# 23_e.net
KiCad netlist of a schematic drawn in EasyEDA Pro
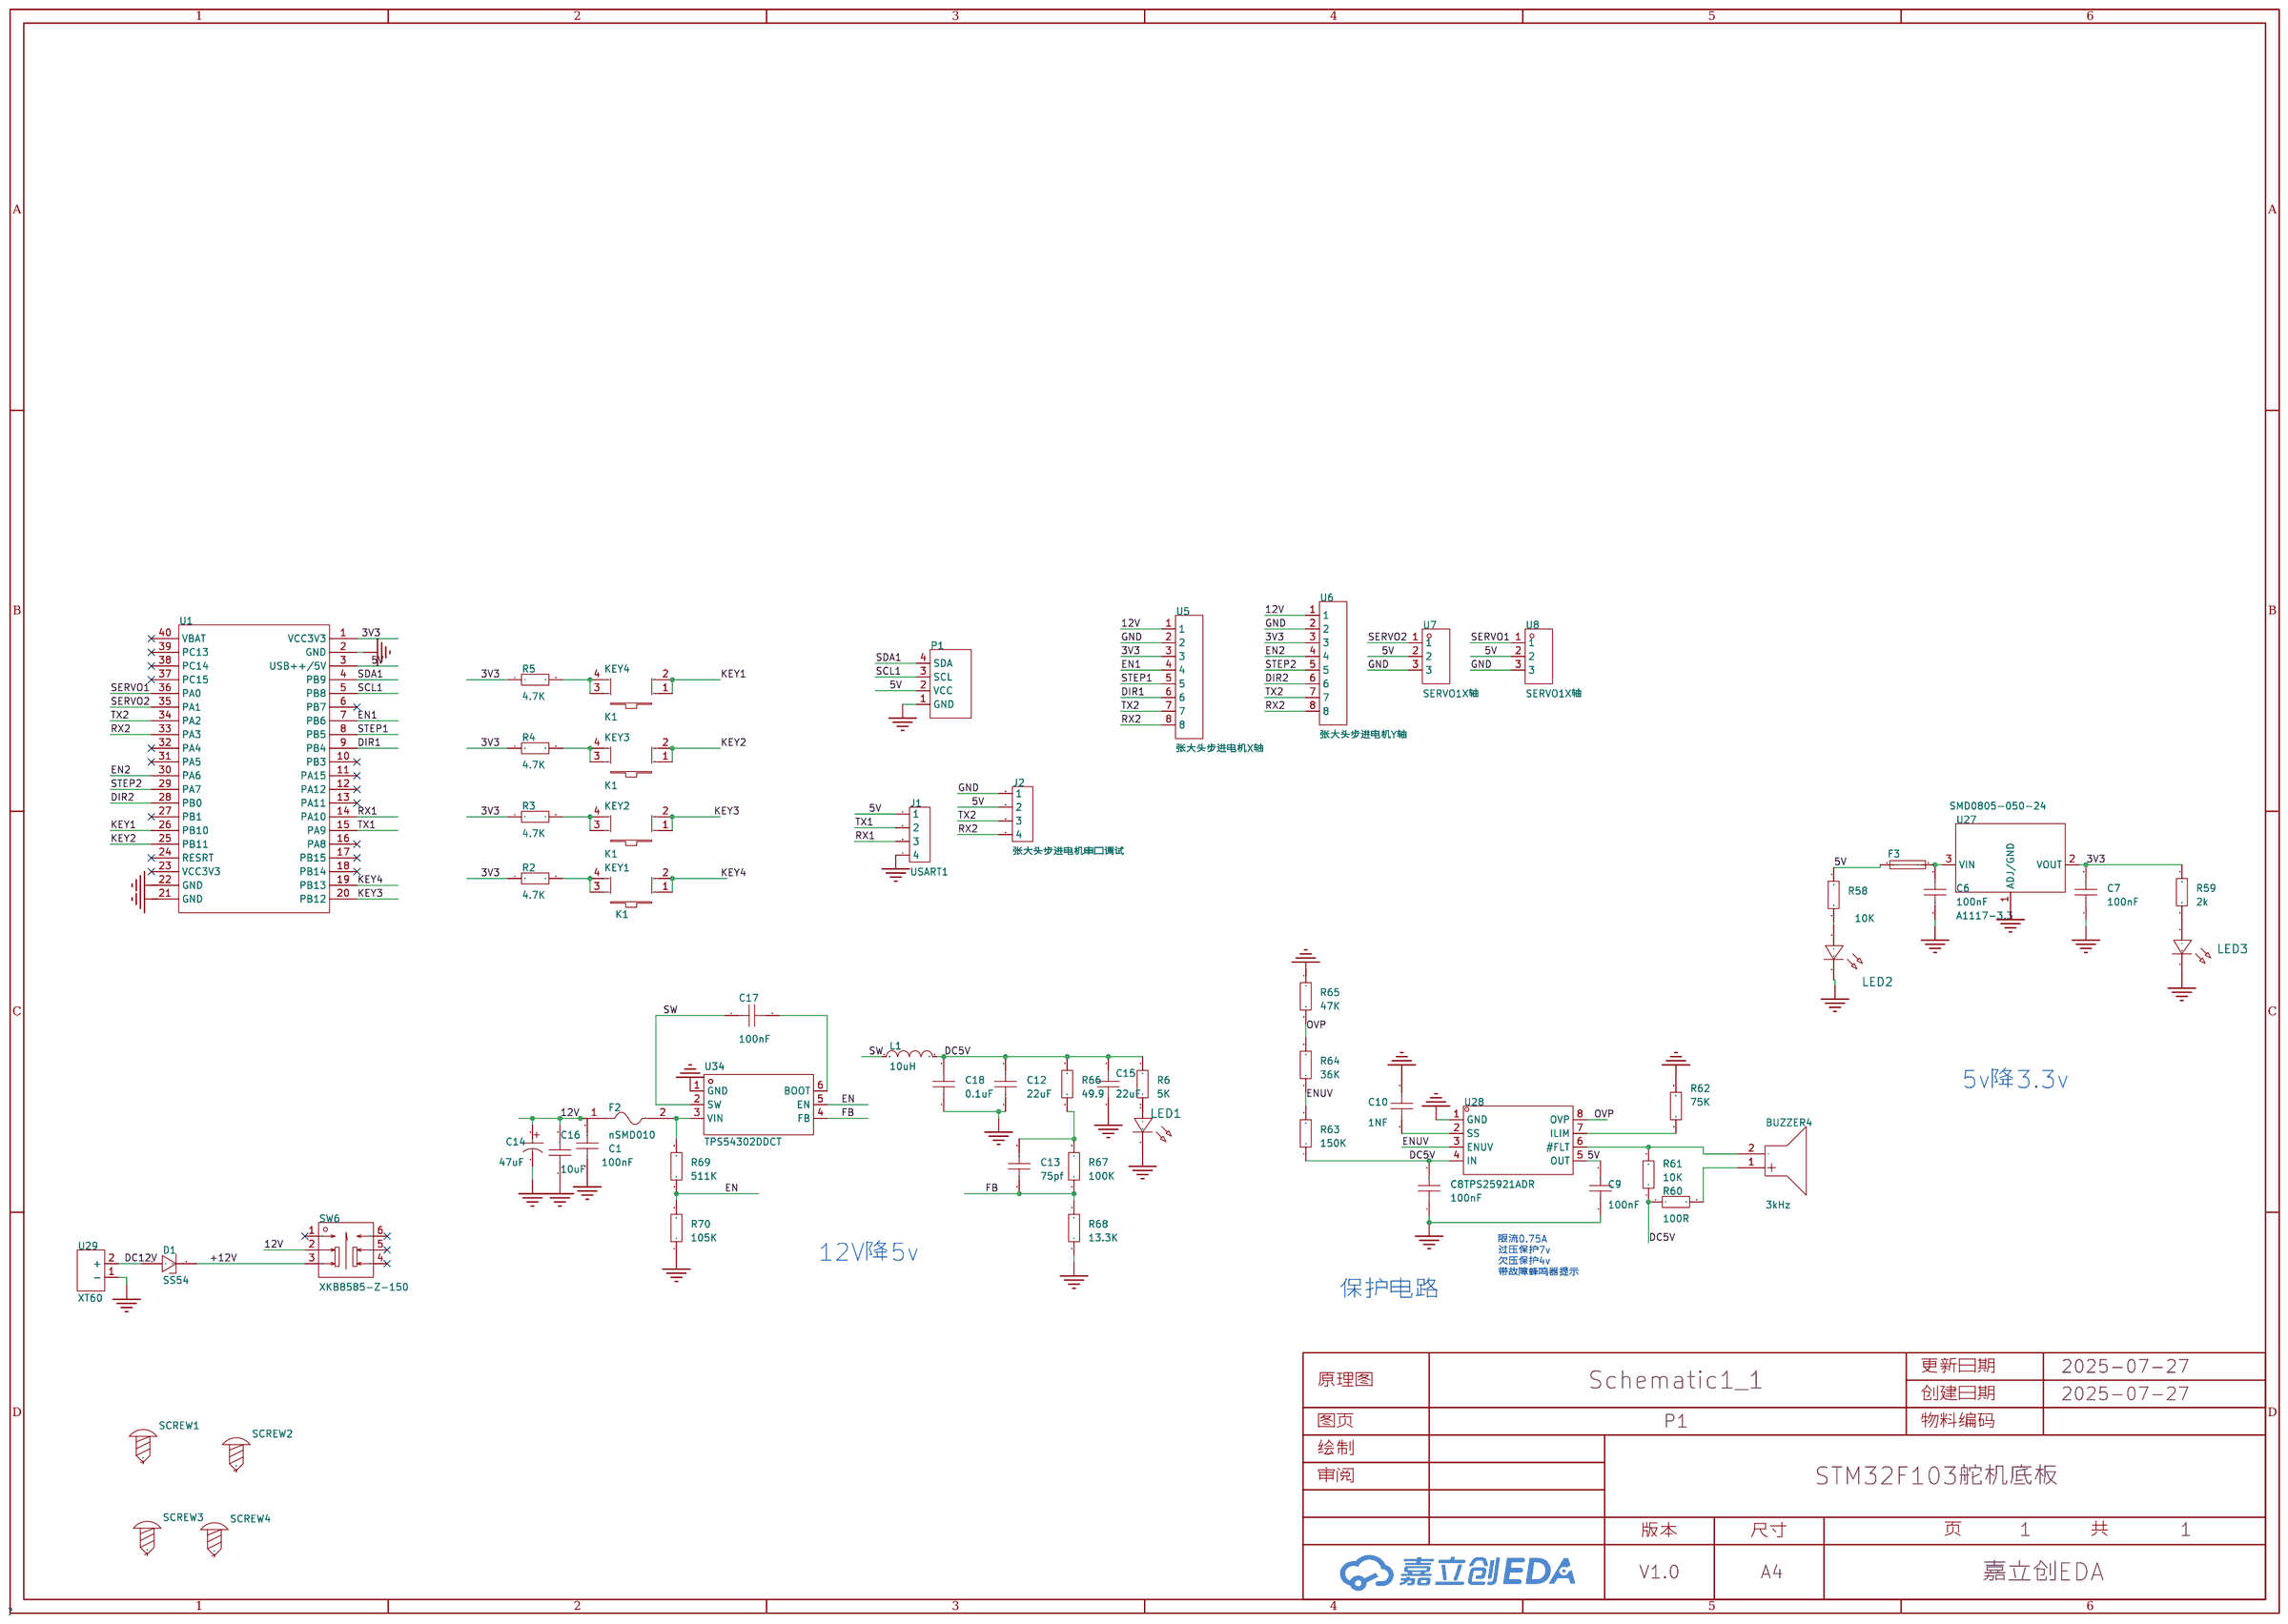
[diagram p0: schematic sheet]

(export (version "E")
  (design (tool "Eeschema 10.0.6"))
  (components
    (comp (ref "BUZZER4")
      (value "3kHz")
      (footprint "easyedapro:BUZ-TH_BD9.0-P5.00-D0.6-FD")
      (description "驱动方式:有源(内含驱动线路);构造类型:电磁式;频率:3kHz;声压(SPL):85dB;")
      (fields (field (name "Manufacturer Part") "HNB09A03") (field (name "Manufacturer") "华能"))
      (libsource (lib "easyedapro") (part "HNB09A03"))
    )
    (comp (ref "C1")
      (value "100nF")
      (footprint "easyedapro:C0603")
      (libsource (lib "easyedapro") (part "CapAcitance"))
    )
    (comp (ref "C6")
      (value "100nF")
      (footprint "easyedapro:C0603")
      (libsource (lib "easyedapro") (part "CapAcitance"))
    )
    (comp (ref "C7")
      (value "100nF")
      (footprint "easyedapro:C0603")
      (libsource (lib "easyedapro") (part "CapAcitance"))
    )
    (comp (ref "C8")
      (value "100nF")
      (footprint "easyedapro:C0603")
      (libsource (lib "easyedapro") (part "CapAcitance"))
    )
    (comp (ref "C9")
      (value "100nF")
      (footprint "easyedapro:C0603")
      (libsource (lib "easyedapro") (part "CapAcitance"))
    )
    (comp (ref "C10")
      (value "1NF")
      (footprint "easyedapro:C0603")
      (libsource (lib "easyedapro") (part "CapAcitance"))
    )
    (comp (ref "C12")
      (value "22uF")
      (footprint "easyedapro:C0603")
      (libsource (lib "easyedapro") (part "CapAcitance"))
    )
    (comp (ref "C13")
      (value "75pf")
      (footprint "easyedapro:C0603")
      (libsource (lib "easyedapro") (part "CapAcitance"))
    )
    (comp (ref "C14")
      (value "47uF")
      (footprint "easyedapro:CAP-TH_BD5.0-P2.00-D0.8-FD")
      (description "容值:47uF;精度:±20%;额定电压:35V;纹波电流:90mA@120Hz;等效串联电阻:-;")
      (fields (field (name "Manufacturer Part") "EWH1VM470D11OT") (field (name "Manufacturer") "AISHI(艾华集团)"))
      (libsource (lib "easyedapro") (part "EWH1VM470D11OT"))
    )
    (comp (ref "C15")
      (value "22uF")
      (footprint "easyedapro:C0603")
      (libsource (lib "easyedapro") (part "CapAcitance"))
    )
    (comp (ref "C16")
      (value "10uF")
      (footprint "easyedapro:C0603")
      (libsource (lib "easyedapro") (part "CapAcitance"))
    )
    (comp (ref "C17")
      (value "100nF")
      (footprint "easyedapro:C0603")
      (libsource (lib "easyedapro") (part "CapAcitance"))
    )
    (comp (ref "C18")
      (value "0.1uF")
      (footprint "easyedapro:C0603")
      (libsource (lib "easyedapro") (part "CapAcitance"))
    )
    (comp (ref "D1")
      (value "SS54")
      (footprint "easyedapro:SMA_L4.3-W2.6-LS5.0-FD")
      (description "二极管配置:独立式;正向压降(Vf):550mV@5.0A;直流反向耐压(Vr):40V;整流电流:5A;")
      (fields (field (name "Manufacturer") "宏迦橙"))
      (libsource (lib "easyedapro") (part "SS54_C7420369"))
    )
    (comp (ref "F2")
      (value "nSMD010")
      (footprint "easyedapro:F1206")
      (description "耐压:60V;最大电流:40A;保持电流(Ih):100mA;跳闸电流:250mA;")
      (fields (field (name "Manufacturer") "台湾陆海"))
      (libsource (lib "easyedapro") (part "nSMD010"))
    )
    (comp (ref "F3")
      (value "SMD0805-050-24")
      (footprint "easyedapro:F0805")
      (description "耐压(Vmax):24V;最大电流(Imax):40A;保持电流(Ihold):500mA;跳闸电流(Itrip):1A;")
      (fields (field (name "Manufacturer") "宏嘉诚"))
      (libsource (lib "easyedapro") (part "SMD0805-050-24"))
    )
    (comp (ref "J1")
      (value "USART1")
      (footprint "easyedapro:XH2.54-4PIN")
      (description "Connector  F=2.54mm  4PIN  插件")
      (fields
        (field (name "Manufacturer Part") "ZX-XH2.54-4PZZ")
        (field (name "Manufacturer") "Megastar(兆星)")
      )
      (libsource (lib "easyedapro") (part "XH2.54-4PIN"))
    )
    (comp (ref "J2")
      (value "张大头步进电机串口调试")
      (footprint "easyedapro:XH2.54-4PIN")
      (description "Connector  F=2.54mm  4PIN  插件")
      (fields
        (field (name "Manufacturer Part") "ZX-XH2.54-4PZZ")
        (field (name "Manufacturer") "Megastar(兆星)")
      )
      (libsource (lib "easyedapro") (part "XH2.54-4PIN"))
    )
    (comp (ref "KEY1")
      (value "K1")
      (footprint "easyedapro:KEY-TH_4P-L6.0-W6.0-P4.50")
      (libsource (lib "easyedapro") (part "button6*6*8.5"))
    )
    (comp (ref "KEY2")
      (value "K1")
      (footprint "easyedapro:KEY-TH_4P-L6.0-W6.0-P4.50")
      (libsource (lib "easyedapro") (part "button6*6*8.5"))
    )
    (comp (ref "KEY3")
      (value "K1")
      (footprint "easyedapro:KEY-TH_4P-L6.0-W6.0-P4.50")
      (libsource (lib "easyedapro") (part "button6*6*8.5"))
    )
    (comp (ref "KEY4")
      (value "K1")
      (footprint "easyedapro:KEY-TH_4P-L6.0-W6.0-P4.50")
      (libsource (lib "easyedapro") (part "button6*6*8.5"))
    )
    (comp (ref "L1")
      (value "10uH")
      (footprint "easyedapro:IND-SMD_L4.0-W4.0")
      (description "电感值:10uH;精度:±20%;额定电流:1.5A;饱和电流(Isat):2.4A;类型:-;")
      (fields (field (name "Manufacturer Part") "SWPA4030S100MT") (field (name "Manufacturer") "Sunlord(顺络)"))
      (libsource (lib "easyedapro") (part "SWPA4030S100MT"))
    )
    (comp (ref "LED1")
      (value "~")
      (footprint "easyedapro:LED_0603")
      (libsource (lib "easyedapro") (part "LED_R"))
    )
    (comp (ref "LED2")
      (value "~")
      (footprint "easyedapro:LED_0603")
      (libsource (lib "easyedapro") (part "LED_R"))
    )
    (comp (ref "LED3")
      (value "~")
      (footprint "easyedapro:LED_0603")
      (libsource (lib "easyedapro") (part "LED_R"))
    )
    (comp (ref "P1")
      (value "~")
      (footprint "easyedapro:OLED-0.96")
      (libsource (lib "easyedapro") (part "OLED0.96_1"))
    )
    (comp (ref "R2")
      (value "4.7K")
      (footprint "easyedapro:R0603")
      (description "电阻类型:厚膜电阻;阻值:49.9kΩ;精度:±1%;功率:100mW;最大工作电压:75V;温度系数:±100ppm/°C;")
      (fields
        (field (name "Manufacturer Part") "0603WAF4992T5E")
        (field (name "Manufacturer") "UNI-ROYAL(厚声)")
      )
      (libsource (lib "easyedapro") (part "0603WAF4992T5E"))
    )
    (comp (ref "R3")
      (value "4.7K")
      (footprint "easyedapro:R0603")
      (description "电阻类型:厚膜电阻;阻值:49.9kΩ;精度:±1%;功率:100mW;最大工作电压:75V;温度系数:±100ppm/°C;")
      (fields
        (field (name "Manufacturer Part") "0603WAF4992T5E")
        (field (name "Manufacturer") "UNI-ROYAL(厚声)")
      )
      (libsource (lib "easyedapro") (part "0603WAF4992T5E"))
    )
    (comp (ref "R4")
      (value "4.7K")
      (footprint "easyedapro:R0603")
      (description "电阻类型:厚膜电阻;阻值:49.9kΩ;精度:±1%;功率:100mW;最大工作电压:75V;温度系数:±100ppm/°C;")
      (fields
        (field (name "Manufacturer Part") "0603WAF4992T5E")
        (field (name "Manufacturer") "UNI-ROYAL(厚声)")
      )
      (libsource (lib "easyedapro") (part "0603WAF4992T5E"))
    )
    (comp (ref "R5")
      (value "4.7K")
      (footprint "easyedapro:R0603")
      (description "电阻类型:厚膜电阻;阻值:49.9kΩ;精度:±1%;功率:100mW;最大工作电压:75V;温度系数:±100ppm/°C;")
      (fields
        (field (name "Manufacturer Part") "0603WAF4992T5E")
        (field (name "Manufacturer") "UNI-ROYAL(厚声)")
      )
      (libsource (lib "easyedapro") (part "0603WAF4992T5E"))
    )
    (comp (ref "R6") (value "5K") (footprint "easyedapro:R0603") (libsource (lib "easyedapro") (part "电阻")))
    (comp (ref "R58") (value "10K") (footprint "easyedapro:R0603") (libsource (lib "easyedapro") (part "电阻")))
    (comp (ref "R59") (value "2k") (footprint "easyedapro:R0603") (libsource (lib "easyedapro") (part "电阻")))
    (comp (ref "R60")
      (value "100R")
      (footprint "easyedapro:R0603")
      (libsource (lib "easyedapro") (part "电阻"))
    )
    (comp (ref "R61") (value "10K") (footprint "easyedapro:R0603") (libsource (lib "easyedapro") (part "电阻")))
    (comp (ref "R62") (value "75K") (footprint "easyedapro:R0603") (libsource (lib "easyedapro") (part "电阻")))
    (comp (ref "R63")
      (value "150K")
      (footprint "easyedapro:R0603")
      (libsource (lib "easyedapro") (part "电阻"))
    )
    (comp (ref "R64") (value "36K") (footprint "easyedapro:R0603") (libsource (lib "easyedapro") (part "电阻")))
    (comp (ref "R65") (value "47K") (footprint "easyedapro:R0603") (libsource (lib "easyedapro") (part "电阻")))
    (comp (ref "R66")
      (value "49.9")
      (footprint "easyedapro:R0603")
      (libsource (lib "easyedapro") (part "电阻"))
    )
    (comp (ref "R67")
      (value "100K")
      (footprint "easyedapro:R0603")
      (libsource (lib "easyedapro") (part "电阻"))
    )
    (comp (ref "R68")
      (value "13.3K")
      (footprint "easyedapro:R0603")
      (libsource (lib "easyedapro") (part "电阻"))
    )
    (comp (ref "R69")
      (value "511K")
      (footprint "easyedapro:R0603")
      (libsource (lib "easyedapro") (part "电阻"))
    )
    (comp (ref "R70")
      (value "105K")
      (footprint "easyedapro:R0603")
      (libsource (lib "easyedapro") (part "电阻"))
    )
    (comp (ref "SCREW1")
      (value "~")
      (footprint "easyedapro:M3螺丝")
      (libsource (lib "easyedapro") (part "螺丝孔"))
    )
    (comp (ref "SCREW2")
      (value "~")
      (footprint "easyedapro:M3螺丝")
      (libsource (lib "easyedapro") (part "螺丝孔"))
    )
    (comp (ref "SCREW3")
      (value "~")
      (footprint "easyedapro:M3螺丝")
      (libsource (lib "easyedapro") (part "螺丝孔"))
    )
    (comp (ref "SCREW4")
      (value "~")
      (footprint "easyedapro:M3螺丝")
      (libsource (lib "easyedapro") (part "螺丝孔"))
    )
    (comp (ref "SW6")
      (value "XKB8585-Z-150")
      (footprint "easyedapro:SW-TH_6P-L8.5-W8.5-P2.50-LS5.4-BL-1_1")
      (description "电路结构:-;自锁/无锁:自锁;安装方式:直插;触点电流:100mA;额定电压 (AC):250V;额定电压 (DC):30V;带灯:不带;作用力:160gf;机械寿命:10万次;")
      (fields (field (name "Manufacturer") "XKB Connectivity(中国星坤)"))
      (libsource (lib "easyedapro") (part "XKB8585-Z-150_1"))
    )
    (comp (ref "U1")
      (value "~")
      (footprint "easyedapro:STM32F103C8T6直插")
      (libsource (lib "easyedapro") (part "STM32F103C8T6直插"))
    )
    (comp (ref "U5")
      (value "张大头步进电机X轴")
      (footprint "easyedapro:CONN-TH_8P-P2.54_XH2.54_C9900012080")
      (libsource (lib "easyedapro") (part "XH2.54-8PIN"))
    )
    (comp (ref "U6")
      (value "张大头步进电机Y轴")
      (footprint "easyedapro:CONN-TH_8P-P2.54_XH2.54_C9900012080")
      (libsource (lib "easyedapro") (part "XH2.54-8PIN"))
    )
    (comp (ref "U7")
      (value "SERVO1X轴")
      (footprint "easyedapro:CONN-TH_XH2.54_3PIN_1")
      (libsource (lib "easyedapro") (part "XH2.54_3PIN_1"))
    )
    (comp (ref "U8")
      (value "SERVO1X轴")
      (footprint "easyedapro:CONN-TH_XH2.54_3PIN_1")
      (libsource (lib "easyedapro") (part "XH2.54_3PIN_1"))
    )
    (comp (ref "U27")
      (value "A1117-3.3")
      (footprint "easyedapro:SOT-223-3_L6.5-W3.4-P2.30-LS7.0-BR-1")
      (description "输出电流:1A;")
      (fields (field (name "Manufacturer") "IDCHIP(英锐芯)"))
      (libsource (lib "easyedapro") (part "A1117-3.3"))
    )
    (comp (ref "U28")
      (value "TPS25921ADR")
      (footprint "easyedapro:SOIC-8_L5.0-W4.0-P1.27-LS6.0-BL")
      (description "TPS25921A 具有自动重试故障响应功能的 4.5V 至 18V、90mΩ、0.4A 至 1.6A 电子保险丝")
      (fields (field (name "Manufacturer") "TI(德州仪器)"))
      (libsource (lib "easyedapro") (part "TPS25921ADR"))
    )
    (comp (ref "U29")
      (value "XT60")
      (footprint "easyedapro:CONN-TH_XT60")
      (description "类别:-;类型1:-;")
      (fields (field (name "Manufacturer") "AMASS(艾迈斯)"))
      (libsource (lib "easyedapro") (part "XT60"))
    )
    (comp (ref "U34")
      (value "TPS54302DDCT")
      (footprint "easyedapro:TSOT-23-6_L2.9-W1.6-P0.95-LS2.8-BR")
      (description "功能类型:降压型;输出类型:可调;工作电压:4.5V~28V;输出电压:596mV~28V;输出电流:3A;")
      (fields (field (name "Manufacturer") "TI(德州仪器)"))
      (libsource (lib "easyedapro") (part "TPS54302DDCT"))
    )
  )
  (nets
    (net (code "1") (name "/+12V") (class "Default")
      (node (ref "D1") (pin "2") (pinfunction "K_2") (pintype "unspecified"))
      (node (ref "SW6") (pin "3") (pinfunction "3_3") (pintype "unspecified"))
    )
    (net (code "2") (name "/3V3") (class "Default")
      (node (ref "C7") (pin "2") (pinfunction "2_2") (pintype "input"))
      (node (ref "R2") (pin "1") (pinfunction "1_1") (pintype "input"))
      (node (ref "R3") (pin "1") (pinfunction "1_1") (pintype "input"))
      (node (ref "R4") (pin "1") (pinfunction "1_1") (pintype "input"))
      (node (ref "R5") (pin "1") (pinfunction "1_1") (pintype "input"))
      (node (ref "R59") (pin "2") (pinfunction "2_2") (pintype "input"))
      (node (ref "U1") (pin "1") (pinfunction "VCC3V3_1") (pintype "input"))
      (node (ref "U27") (pin "2") (pinfunction "VOUT_2") (pintype "unspecified"))
      (node (ref "U5") (pin "3") (pinfunction "3_3") (pintype "unspecified"))
      (node (ref "U6") (pin "3") (pinfunction "3_3") (pintype "unspecified"))
    )
    (net (code "3") (name "/5V") (class "Default")
      (node (ref "C9") (pin "2") (pinfunction "2_2") (pintype "input"))
      (node (ref "F3") (pin "1") (pinfunction "1_1") (pintype "unspecified"))
      (node (ref "J1") (pin "1") (pinfunction "1_1") (pintype "unspecified"))
      (node (ref "J2") (pin "2") (pinfunction "2_2") (pintype "unspecified"))
      (node (ref "P1") (pin "2") (pinfunction "VCC_2") (pintype "input"))
      (node (ref "R58") (pin "2") (pinfunction "2_2") (pintype "input"))
      (node (ref "U1") (pin "3") (pinfunction "USB++/5V_3") (pintype "input"))
      (node (ref "U28") (pin "5") (pinfunction "OUT_5") (pintype "unspecified"))
      (node (ref "U7") (pin "2") (pinfunction "2_2") (pintype "unspecified"))
      (node (ref "U8") (pin "2") (pinfunction "2_2") (pintype "unspecified"))
    )
    (net (code "4") (name "/12V") (class "Default")
      (node (ref "C1") (pin "2") (pinfunction "2_2") (pintype "input"))
      (node (ref "C14") (pin "1") (pinfunction "1_1") (pintype "input"))
      (node (ref "C16") (pin "2") (pinfunction "2_2") (pintype "input"))
      (node (ref "F2") (pin "1") (pinfunction "1_1") (pintype "unspecified"))
      (node (ref "SW6") (pin "2") (pinfunction "2_2") (pintype "unspecified"))
      (node (ref "U5") (pin "1") (pinfunction "1_1") (pintype "unspecified"))
      (node (ref "U6") (pin "1") (pinfunction "1_1") (pintype "unspecified"))
    )
    (net (code "5") (name "/DC5V") (class "Default")
      (node (ref "C12") (pin "2") (pinfunction "2_2") (pintype "input"))
      (node (ref "C15") (pin "2") (pinfunction "2_2") (pintype "input"))
      (node (ref "C18") (pin "2") (pinfunction "2_2") (pintype "input"))
      (node (ref "C8") (pin "2") (pinfunction "2_2") (pintype "input"))
      (node (ref "L1") (pin "2") (pinfunction "2_2") (pintype "unspecified"))
      (node (ref "R6") (pin "2") (pinfunction "2_2") (pintype "input"))
      (node (ref "R60") (pin "1") (pinfunction "1_1") (pintype "input"))
      (node (ref "R61") (pin "1") (pinfunction "1_1") (pintype "input"))
      (node (ref "R63") (pin "1") (pinfunction "1_1") (pintype "input"))
      (node (ref "R66") (pin "2") (pinfunction "2_2") (pintype "input"))
      (node (ref "U28") (pin "4") (pinfunction "IN_4") (pintype "unspecified"))
    )
    (net (code "6") (name "/DC12V") (class "Default")
      (node (ref "D1") (pin "1") (pinfunction "A_1") (pintype "unspecified"))
      (node (ref "U29") (pin "2") (pinfunction "+_2") (pintype "unspecified"))
    )
    (net (code "7") (name "/DIR1") (class "Default")
      (node (ref "U1") (pin "9") (pinfunction "PB4_9") (pintype "input"))
      (node (ref "U5") (pin "6") (pinfunction "6_6") (pintype "unspecified"))
    )
    (net (code "8") (name "/DIR2") (class "Default")
      (node (ref "U1") (pin "28") (pinfunction "PB0_28") (pintype "input"))
      (node (ref "U6") (pin "6") (pinfunction "6_6") (pintype "unspecified"))
    )
    (net (code "9") (name "/EN") (class "Default")
      (node (ref "R69") (pin "1") (pinfunction "1_1") (pintype "input"))
      (node (ref "R70") (pin "2") (pinfunction "2_2") (pintype "input"))
      (node (ref "U34") (pin "5") (pinfunction "EN_5") (pintype "unspecified"))
    )
    (net (code "10") (name "/EN1") (class "Default")
      (node (ref "U1") (pin "7") (pinfunction "PB6_7") (pintype "input"))
      (node (ref "U5") (pin "4") (pinfunction "4_4") (pintype "unspecified"))
    )
    (net (code "11") (name "/EN2") (class "Default")
      (node (ref "U1") (pin "30") (pinfunction "PA6_30") (pintype "input"))
      (node (ref "U6") (pin "4") (pinfunction "4_4") (pintype "unspecified"))
    )
    (net (code "12") (name "/ENUV") (class "Default")
      (node (ref "R63") (pin "2") (pinfunction "2_2") (pintype "input"))
      (node (ref "R64") (pin "1") (pinfunction "1_1") (pintype "input"))
      (node (ref "U28") (pin "3") (pinfunction "ENUV_3") (pintype "unspecified"))
    )
    (net (code "13") (name "/FB") (class "Default")
      (node (ref "C13") (pin "1") (pinfunction "1_1") (pintype "input"))
      (node (ref "R67") (pin "1") (pinfunction "1_1") (pintype "input"))
      (node (ref "R68") (pin "2") (pinfunction "2_2") (pintype "input"))
      (node (ref "U34") (pin "4") (pinfunction "FB_4") (pintype "unspecified"))
    )
    (net (code "14") (name "/KEY1") (class "Default")
      (node (ref "KEY4") (pin "1") (pinfunction "1_1") (pintype "input"))
      (node (ref "KEY4") (pin "2") (pinfunction "2_2") (pintype "input"))
      (node (ref "U1") (pin "26") (pinfunction "PB10_26") (pintype "input"))
    )
    (net (code "15") (name "/KEY2") (class "Default")
      (node (ref "KEY3") (pin "1") (pinfunction "1_1") (pintype "input"))
      (node (ref "KEY3") (pin "2") (pinfunction "2_2") (pintype "input"))
      (node (ref "U1") (pin "25") (pinfunction "PB11_25") (pintype "input"))
    )
    (net (code "16") (name "/KEY3") (class "Default")
      (node (ref "KEY2") (pin "1") (pinfunction "1_1") (pintype "input"))
      (node (ref "KEY2") (pin "2") (pinfunction "2_2") (pintype "input"))
      (node (ref "U1") (pin "20") (pinfunction "PB12_20") (pintype "input"))
    )
    (net (code "17") (name "/KEY4") (class "Default")
      (node (ref "KEY1") (pin "1") (pinfunction "1_1") (pintype "input"))
      (node (ref "KEY1") (pin "2") (pinfunction "2_2") (pintype "input"))
      (node (ref "U1") (pin "19") (pinfunction "PB13_19") (pintype "input"))
    )
    (net (code "18") (name "/OVP") (class "Default")
      (node (ref "R64") (pin "2") (pinfunction "2_2") (pintype "input"))
      (node (ref "R65") (pin "2") (pinfunction "2_2") (pintype "input"))
      (node (ref "U28") (pin "8") (pinfunction "OVP_8") (pintype "unspecified"))
    )
    (net (code "19") (name "/RX1") (class "Default")
      (node (ref "J1") (pin "3") (pinfunction "3_3") (pintype "unspecified"))
      (node (ref "U1") (pin "14") (pinfunction "PA10_14") (pintype "input"))
    )
    (net (code "20") (name "/RX2") (class "Default")
      (node (ref "J2") (pin "4") (pinfunction "4_4") (pintype "unspecified"))
      (node (ref "U1") (pin "33") (pinfunction "PA3_33") (pintype "input"))
      (node (ref "U5") (pin "8") (pinfunction "8_8") (pintype "unspecified"))
      (node (ref "U6") (pin "8") (pinfunction "8_8") (pintype "unspecified"))
    )
    (net (code "21") (name "/SCL1") (class "Default")
      (node (ref "P1") (pin "3") (pinfunction "SCL_3") (pintype "input"))
      (node (ref "U1") (pin "5") (pinfunction "PB8_5") (pintype "input"))
    )
    (net (code "22") (name "/SDA1") (class "Default")
      (node (ref "P1") (pin "4") (pinfunction "SDA_4") (pintype "input"))
      (node (ref "U1") (pin "4") (pinfunction "PB9_4") (pintype "input"))
    )
    (net (code "23") (name "/SERVO1") (class "Default")
      (node (ref "U1") (pin "36") (pinfunction "PA0_36") (pintype "input"))
      (node (ref "U8") (pin "1") (pinfunction "1_1") (pintype "unspecified"))
    )
    (net (code "24") (name "/SERVO2") (class "Default")
      (node (ref "U1") (pin "35") (pinfunction "PA1_35") (pintype "input"))
      (node (ref "U7") (pin "1") (pinfunction "1_1") (pintype "unspecified"))
    )
    (net (code "25") (name "/STEP1") (class "Default")
      (node (ref "U1") (pin "8") (pinfunction "PB5_8") (pintype "input"))
      (node (ref "U5") (pin "5") (pinfunction "5_5") (pintype "unspecified"))
    )
    (net (code "26") (name "/STEP2") (class "Default")
      (node (ref "U1") (pin "29") (pinfunction "PA7_29") (pintype "input"))
      (node (ref "U6") (pin "5") (pinfunction "5_5") (pintype "unspecified"))
    )
    (net (code "27") (name "/SW") (class "Default")
      (node (ref "C17") (pin "1") (pinfunction "1_1") (pintype "input"))
      (node (ref "L1") (pin "1") (pinfunction "1_1") (pintype "unspecified"))
      (node (ref "U34") (pin "2") (pinfunction "SW_2") (pintype "unspecified"))
    )
    (net (code "28") (name "/TX1") (class "Default")
      (node (ref "J1") (pin "2") (pinfunction "2_2") (pintype "unspecified"))
      (node (ref "U1") (pin "15") (pinfunction "PA9_15") (pintype "input"))
    )
    (net (code "29") (name "/TX2") (class "Default")
      (node (ref "J2") (pin "3") (pinfunction "3_3") (pintype "unspecified"))
      (node (ref "U1") (pin "34") (pinfunction "PA2_34") (pintype "input"))
      (node (ref "U5") (pin "7") (pinfunction "7_7") (pintype "unspecified"))
      (node (ref "U6") (pin "7") (pinfunction "7_7") (pintype "unspecified"))
    )
    (net (code "30") (name "GND") (class "Default")
      (node (ref "C1") (pin "1") (pinfunction "1_1") (pintype "input"))
      (node (ref "C10") (pin "1") (pinfunction "1_1") (pintype "input"))
      (node (ref "C12") (pin "1") (pinfunction "1_1") (pintype "input"))
      (node (ref "C14") (pin "2") (pinfunction "2_2") (pintype "input"))
      (node (ref "C15") (pin "1") (pinfunction "1_1") (pintype "input"))
      (node (ref "C16") (pin "1") (pinfunction "1_1") (pintype "input"))
      (node (ref "C18") (pin "1") (pinfunction "1_1") (pintype "input"))
      (node (ref "C6") (pin "1") (pinfunction "1_1") (pintype "input"))
      (node (ref "C7") (pin "1") (pinfunction "1_1") (pintype "input"))
      (node (ref "C8") (pin "1") (pinfunction "1_1") (pintype "input"))
      (node (ref "C9") (pin "1") (pinfunction "1_1") (pintype "input"))
      (node (ref "J1") (pin "4") (pinfunction "4_4") (pintype "unspecified"))
      (node (ref "J2") (pin "1") (pinfunction "1_1") (pintype "unspecified"))
      (node (ref "LED1") (pin "1") (pinfunction "C_1") (pintype "input"))
      (node (ref "LED2") (pin "1") (pinfunction "C_1") (pintype "input"))
      (node (ref "LED3") (pin "1") (pinfunction "C_1") (pintype "input"))
      (node (ref "P1") (pin "1") (pinfunction "GND_1") (pintype "input"))
      (node (ref "R62") (pin "2") (pinfunction "2_2") (pintype "input"))
      (node (ref "R65") (pin "1") (pinfunction "1_1") (pintype "input"))
      (node (ref "R68") (pin "1") (pinfunction "1_1") (pintype "input"))
      (node (ref "R70") (pin "1") (pinfunction "1_1") (pintype "input"))
      (node (ref "U1") (pin "2") (pinfunction "GND_2") (pintype "input"))
      (node (ref "U1") (pin "21") (pinfunction "GND_21") (pintype "input"))
      (node (ref "U1") (pin "22") (pinfunction "GND_22") (pintype "input"))
      (node (ref "U27") (pin "1") (pinfunction "ADJ/GND_1") (pintype "unspecified"))
      (node (ref "U28") (pin "1") (pinfunction "GND_1") (pintype "unspecified"))
      (node (ref "U29") (pin "1") (pinfunction "-_1") (pintype "unspecified"))
      (node (ref "U34") (pin "1") (pinfunction "GND_1") (pintype "unspecified"))
      (node (ref "U5") (pin "2") (pinfunction "2_2") (pintype "unspecified"))
      (node (ref "U6") (pin "2") (pinfunction "2_2") (pintype "unspecified"))
      (node (ref "U7") (pin "3") (pinfunction "3_3") (pintype "unspecified"))
      (node (ref "U8") (pin "3") (pinfunction "3_3") (pintype "unspecified"))
    )
    (net (code "31") (name "Net-(BUZZER4-+)") (class "Default")
      (node (ref "BUZZER4") (pin "1") (pinfunction "+_1") (pintype "unspecified"))
      (node (ref "R60") (pin "2") (pinfunction "2_2") (pintype "input"))
    )
    (net (code "32") (name "Net-(BUZZER4--)") (class "Default")
      (node (ref "BUZZER4") (pin "2") (pinfunction "-_2") (pintype "unspecified"))
      (node (ref "R61") (pin "2") (pinfunction "2_2") (pintype "input"))
      (node (ref "U28") (pin "6") (pinfunction "#FLT_6") (pintype "unspecified"))
    )
    (net (code "33") (name "Net-(C13-Pad2)") (class "Default")
      (node (ref "C13") (pin "2") (pinfunction "2_2") (pintype "input"))
      (node (ref "R66") (pin "1") (pinfunction "1_1") (pintype "input"))
      (node (ref "R67") (pin "2") (pinfunction "2_2") (pintype "input"))
    )
    (net (code "34") (name "Net-(KEY1-Pad3)") (class "Default")
      (node (ref "KEY1") (pin "3") (pinfunction "3_3") (pintype "input"))
      (node (ref "KEY1") (pin "4") (pinfunction "4_4") (pintype "input"))
      (node (ref "R2") (pin "2") (pinfunction "2_2") (pintype "input"))
    )
    (net (code "35") (name "Net-(KEY2-Pad3)") (class "Default")
      (node (ref "KEY2") (pin "3") (pinfunction "3_3") (pintype "input"))
      (node (ref "KEY2") (pin "4") (pinfunction "4_4") (pintype "input"))
      (node (ref "R3") (pin "2") (pinfunction "2_2") (pintype "input"))
    )
    (net (code "36") (name "Net-(KEY3-Pad3)") (class "Default")
      (node (ref "KEY3") (pin "3") (pinfunction "3_3") (pintype "input"))
      (node (ref "KEY3") (pin "4") (pinfunction "4_4") (pintype "input"))
      (node (ref "R4") (pin "2") (pinfunction "2_2") (pintype "input"))
    )
    (net (code "37") (name "Net-(KEY4-Pad3)") (class "Default")
      (node (ref "KEY4") (pin "3") (pinfunction "3_3") (pintype "input"))
      (node (ref "KEY4") (pin "4") (pinfunction "4_4") (pintype "input"))
      (node (ref "R5") (pin "2") (pinfunction "2_2") (pintype "input"))
    )
    (net (code "38") (name "Net-(LED1-A)") (class "Default")
      (node (ref "LED1") (pin "2") (pinfunction "A_2") (pintype "input"))
      (node (ref "R6") (pin "1") (pinfunction "1_1") (pintype "input"))
    )
    (net (code "39") (name "Net-(LED2-A)") (class "Default")
      (node (ref "LED2") (pin "2") (pinfunction "A_2") (pintype "input"))
      (node (ref "R58") (pin "1") (pinfunction "1_1") (pintype "input"))
    )
    (net (code "40") (name "Net-(LED3-A)") (class "Default")
      (node (ref "LED3") (pin "2") (pinfunction "A_2") (pintype "input"))
      (node (ref "R59") (pin "1") (pinfunction "1_1") (pintype "input"))
    )
    (net (code "41") (name "Net-(U27-VIN)") (class "Default")
      (node (ref "C6") (pin "2") (pinfunction "2_2") (pintype "input"))
      (node (ref "F3") (pin "2") (pinfunction "2_2") (pintype "unspecified"))
      (node (ref "U27") (pin "3") (pinfunction "VIN_3") (pintype "unspecified"))
    )
    (net (code "42") (name "Net-(U28-ILIM)") (class "Default")
      (node (ref "R62") (pin "1") (pinfunction "1_1") (pintype "input"))
      (node (ref "U28") (pin "7") (pinfunction "ILIM_7") (pintype "unspecified"))
    )
    (net (code "43") (name "Net-(U28-SS)") (class "Default")
      (node (ref "C10") (pin "2") (pinfunction "2_2") (pintype "input"))
      (node (ref "U28") (pin "2") (pinfunction "SS_2") (pintype "unspecified"))
    )
    (net (code "44") (name "Net-(U34-BOOT)") (class "Default")
      (node (ref "C17") (pin "2") (pinfunction "2_2") (pintype "input"))
      (node (ref "U34") (pin "6") (pinfunction "BOOT_6") (pintype "unspecified"))
    )
    (net (code "45") (name "Net-(U34-VIN)") (class "Default")
      (node (ref "F2") (pin "2") (pinfunction "2_2") (pintype "unspecified"))
      (node (ref "R69") (pin "2") (pinfunction "2_2") (pintype "input"))
      (node (ref "U34") (pin "3") (pinfunction "VIN_3") (pintype "unspecified"))
    )
    (net (code "46") (name "unconnected-(SCREW1-Pad1)") (class "Default")
      (node (ref "SCREW1") (pin "1") (pinfunction "1_1") (pintype "input"))
    )
    (net (code "47") (name "unconnected-(SCREW2-Pad1)") (class "Default")
      (node (ref "SCREW2") (pin "1") (pinfunction "1_1") (pintype "input"))
    )
    (net (code "48") (name "unconnected-(SCREW3-Pad1)") (class "Default")
      (node (ref "SCREW3") (pin "1") (pinfunction "1_1") (pintype "input"))
    )
    (net (code "49") (name "unconnected-(SCREW4-Pad1)") (class "Default")
      (node (ref "SCREW4") (pin "1") (pinfunction "1_1") (pintype "input"))
    )
    (net (code "50") (name "unconnected-(SW6-Pad1)") (class "Default")
      (node (ref "SW6") (pin "1") (pinfunction "1_1") (pintype "unspecified+no_connect"))
    )
    (net (code "51") (name "unconnected-(SW6-Pad4)") (class "Default")
      (node (ref "SW6") (pin "4") (pinfunction "4_4") (pintype "unspecified+no_connect"))
    )
    (net (code "52") (name "unconnected-(SW6-Pad5)") (class "Default")
      (node (ref "SW6") (pin "5") (pinfunction "5_5") (pintype "unspecified+no_connect"))
    )
    (net (code "53") (name "unconnected-(SW6-Pad6)") (class "Default")
      (node (ref "SW6") (pin "6") (pinfunction "6_6") (pintype "unspecified+no_connect"))
    )
    (net (code "54") (name "unconnected-(U1-PA4-Pad32)") (class "Default")
      (node (ref "U1") (pin "32") (pinfunction "PA4_32") (pintype "input+no_connect"))
    )
    (net (code "55") (name "unconnected-(U1-PA5-Pad31)") (class "Default")
      (node (ref "U1") (pin "31") (pinfunction "PA5_31") (pintype "input+no_connect"))
    )
    (net (code "56") (name "unconnected-(U1-PA8-Pad16)") (class "Default")
      (node (ref "U1") (pin "16") (pinfunction "PA8_16") (pintype "input+no_connect"))
    )
    (net (code "57") (name "unconnected-(U1-PA11-Pad13)") (class "Default")
      (node (ref "U1") (pin "13") (pinfunction "PA11_13") (pintype "input+no_connect"))
    )
    (net (code "58") (name "unconnected-(U1-PA12-Pad12)") (class "Default")
      (node (ref "U1") (pin "12") (pinfunction "PA12_12") (pintype "input+no_connect"))
    )
    (net (code "59") (name "unconnected-(U1-PA15-Pad11)") (class "Default")
      (node (ref "U1") (pin "11") (pinfunction "PA15_11") (pintype "input+no_connect"))
    )
    (net (code "60") (name "unconnected-(U1-PB1-Pad27)") (class "Default")
      (node (ref "U1") (pin "27") (pinfunction "PB1_27") (pintype "input+no_connect"))
    )
    (net (code "61") (name "unconnected-(U1-PB3-Pad10)") (class "Default")
      (node (ref "U1") (pin "10") (pinfunction "PB3_10") (pintype "input+no_connect"))
    )
    (net (code "62") (name "unconnected-(U1-PB7-Pad6)") (class "Default")
      (node (ref "U1") (pin "6") (pinfunction "PB7_6") (pintype "input+no_connect"))
    )
    (net (code "63") (name "unconnected-(U1-PB14-Pad18)") (class "Default")
      (node (ref "U1") (pin "18") (pinfunction "PB14_18") (pintype "input+no_connect"))
    )
    (net (code "64") (name "unconnected-(U1-PB15-Pad17)") (class "Default")
      (node (ref "U1") (pin "17") (pinfunction "PB15_17") (pintype "input+no_connect"))
    )
    (net (code "65") (name "unconnected-(U1-PC13-Pad39)") (class "Default")
      (node (ref "U1") (pin "39") (pinfunction "PC13_39") (pintype "input+no_connect"))
    )
    (net (code "66") (name "unconnected-(U1-PC14-Pad38)") (class "Default")
      (node (ref "U1") (pin "38") (pinfunction "PC14_38") (pintype "input+no_connect"))
    )
    (net (code "67") (name "unconnected-(U1-PC15-Pad37)") (class "Default")
      (node (ref "U1") (pin "37") (pinfunction "PC15_37") (pintype "input+no_connect"))
    )
    (net (code "68") (name "unconnected-(U1-RESRT-Pad24)") (class "Default")
      (node (ref "U1") (pin "24") (pinfunction "RESRT_24") (pintype "input+no_connect"))
    )
    (net (code "69") (name "unconnected-(U1-VBAT-Pad40)") (class "Default")
      (node (ref "U1") (pin "40") (pinfunction "VBAT_40") (pintype "input+no_connect"))
    )
    (net (code "70") (name "unconnected-(U1-VCC3V3-Pad23)") (class "Default")
      (node (ref "U1") (pin "23") (pinfunction "VCC3V3_23") (pintype "input+no_connect"))
    )
  )
)
